# pc_tinyGSR.net
KiCad netlist of a schematic drawn in EAGLE
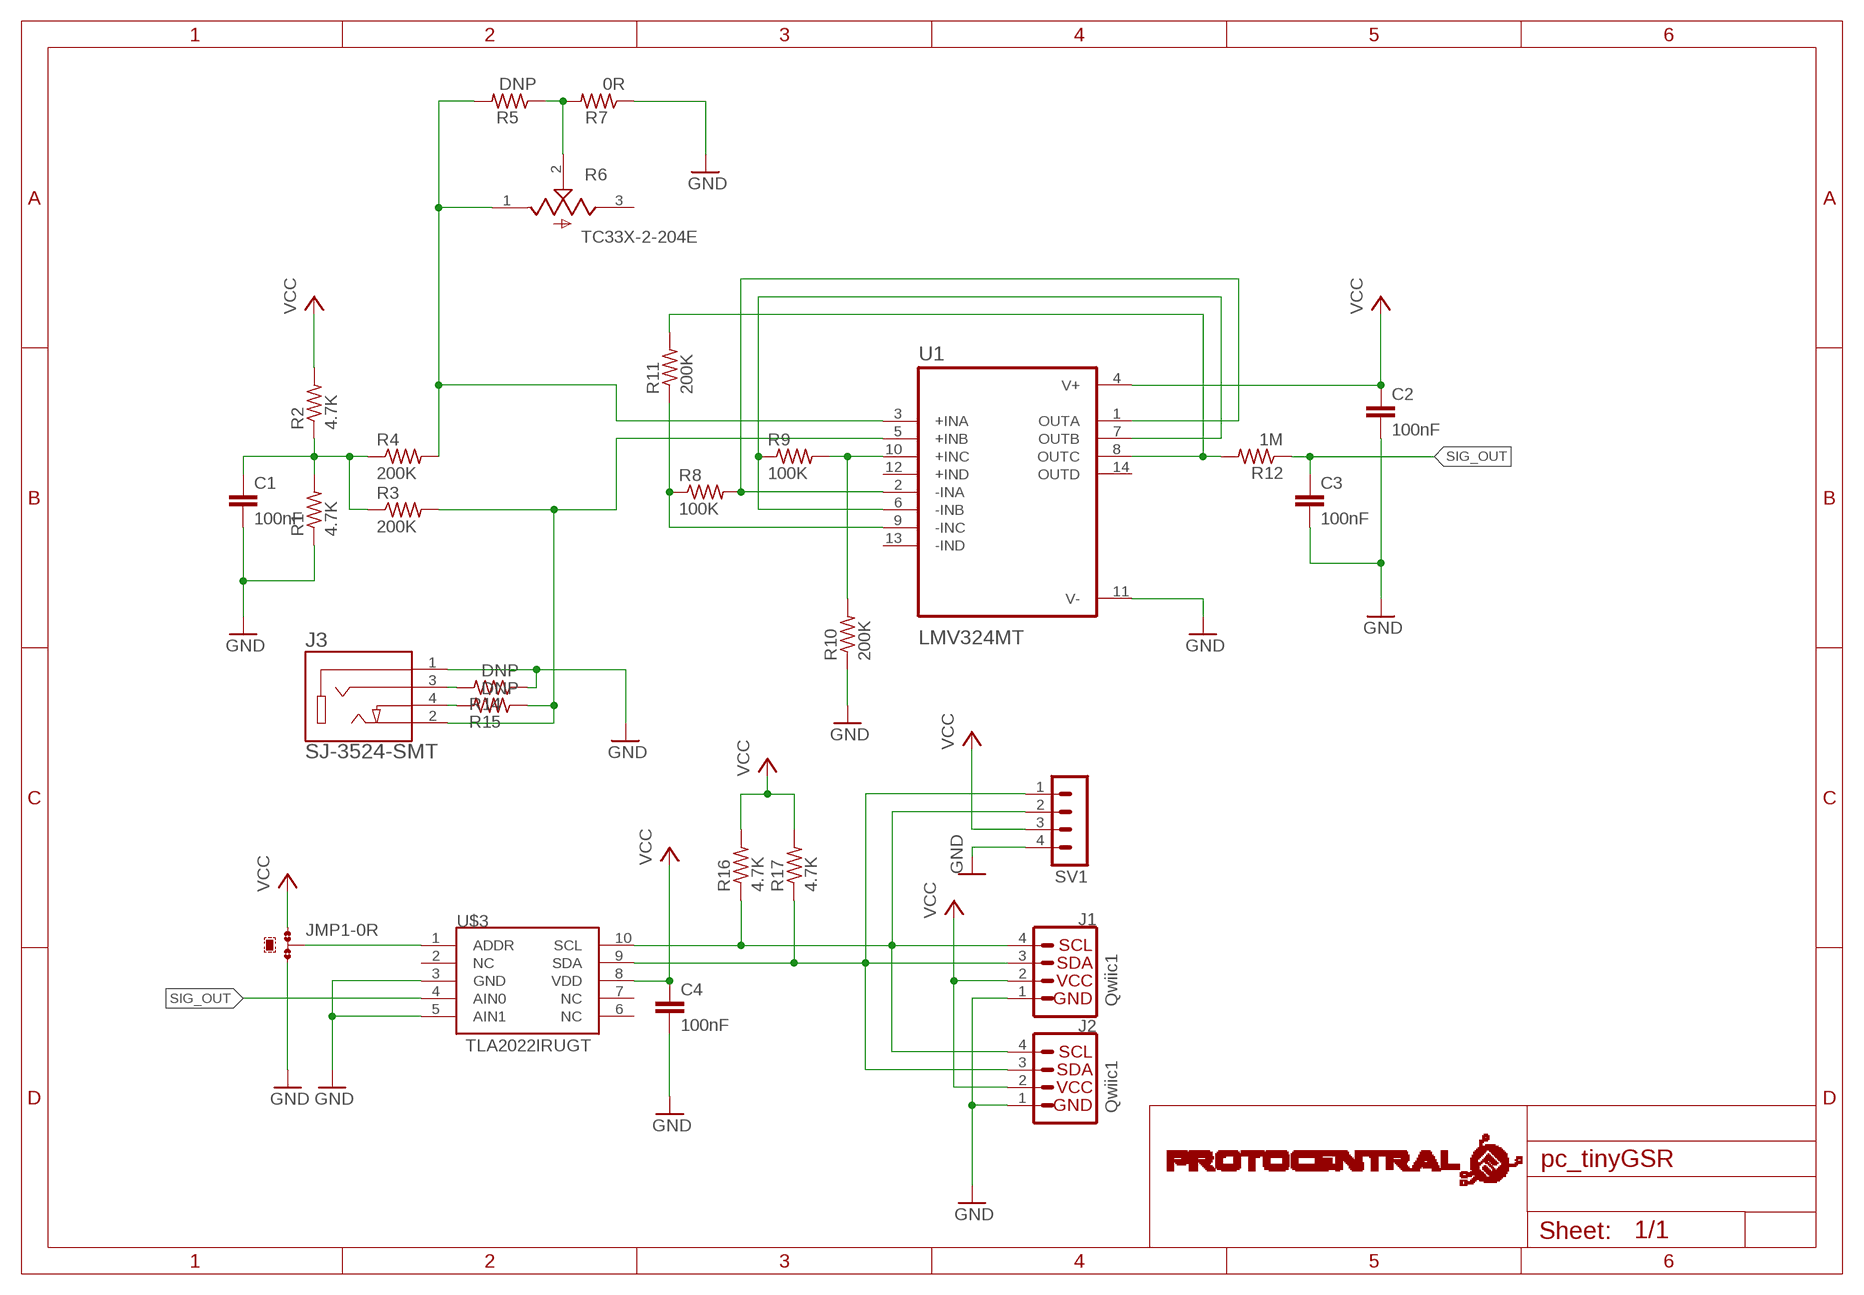
[diagram p0: schematic, sheet 1]

(export (version "E")
  (design (tool "Eeschema 10.0.6"))
  (components
    (comp (ref "C1")
      (value "100nF")
      (footprint "eagle-import:C0402")
      (libsource (lib "eagle-import") (part "C-EUC0402"))
    )
    (comp (ref "C2")
      (value "100nF")
      (footprint "eagle-import:C0402")
      (libsource (lib "eagle-import") (part "C-EUC0402"))
    )
    (comp (ref "C3")
      (value "100nF")
      (footprint "eagle-import:C0402")
      (libsource (lib "eagle-import") (part "C-EUC0402"))
    )
    (comp (ref "C4")
      (value "100nF")
      (footprint "eagle-import:C0402")
      (libsource (lib "eagle-import") (part "C-EUC0402"))
    )
    (comp (ref "J1")
      (value "Qwiic1")
      (footprint "eagle-import:1X04_1MM_RA")
      (libsource (lib "eagle-import") (part "QWIIC_CONNECTORJS-1MM"))
    )
    (comp (ref "J2")
      (value "Qwiic1")
      (footprint "eagle-import:1X04_1MM_RA")
      (libsource (lib "eagle-import") (part "QWIIC_CONNECTORJS-1MM"))
    )
    (comp (ref "J3")
      (value "SJ-3524-SMT")
      (footprint "eagle-import:CUI_SJ-3524-SMT")
      (fields (field (name "MF") "CUI Devices") (field (name "MP") "SJ-3524-SMT-TR"))
      (libsource (lib "eagle-import") (part "SJ-3524-SMT"))
    )
    (comp (ref "JMP1")
      (value "0R-JUMPA")
      (footprint "eagle-import:A0R-JMP")
      (libsource (lib "eagle-import") (part "0R-JUMPA"))
    )
    (comp (ref "R1")
      (value "4.7K")
      (footprint "eagle-import:R0402")
      (libsource (lib "eagle-import") (part "R-US_R0402"))
    )
    (comp (ref "R2")
      (value "4.7K")
      (footprint "eagle-import:R0402")
      (libsource (lib "eagle-import") (part "R-US_R0402"))
    )
    (comp (ref "R3")
      (value "200K")
      (footprint "eagle-import:R0402")
      (libsource (lib "eagle-import") (part "R-US_R0402"))
    )
    (comp (ref "R4")
      (value "200K")
      (footprint "eagle-import:R0402")
      (libsource (lib "eagle-import") (part "R-US_R0402"))
    )
    (comp (ref "R5")
      (value "DNP")
      (footprint "eagle-import:R0402")
      (libsource (lib "eagle-import") (part "R-US_R0402"))
    )
    (comp (ref "R6")
      (value "TC33X-2-204E")
      (footprint "eagle-import:TRIM_TC33X-2-204E")
      (fields (field (name "MF") "Bourns"))
      (libsource (lib "eagle-import") (part "TC33X-2-204E"))
    )
    (comp (ref "R7")
      (value "0R")
      (footprint "eagle-import:R0402")
      (libsource (lib "eagle-import") (part "R-US_R0402"))
    )
    (comp (ref "R8")
      (value "100K")
      (footprint "eagle-import:R0402")
      (libsource (lib "eagle-import") (part "R-US_R0402"))
    )
    (comp (ref "R9")
      (value "100K")
      (footprint "eagle-import:R0402")
      (libsource (lib "eagle-import") (part "R-US_R0402"))
    )
    (comp (ref "R10")
      (value "200K")
      (footprint "eagle-import:R0402")
      (libsource (lib "eagle-import") (part "R-US_R0402"))
    )
    (comp (ref "R11")
      (value "200K")
      (footprint "eagle-import:R0402")
      (libsource (lib "eagle-import") (part "R-US_R0402"))
    )
    (comp (ref "R12")
      (value "1M")
      (footprint "eagle-import:R0402")
      (libsource (lib "eagle-import") (part "R-US_R0402"))
    )
    (comp (ref "R14")
      (value "DNP")
      (footprint "eagle-import:R0402")
      (libsource (lib "eagle-import") (part "R-US_R0402"))
    )
    (comp (ref "R15")
      (value "DNP")
      (footprint "eagle-import:R0402")
      (libsource (lib "eagle-import") (part "R-US_R0402"))
    )
    (comp (ref "R16")
      (value "4.7K")
      (footprint "eagle-import:R0402")
      (libsource (lib "eagle-import") (part "R-US_R0402"))
    )
    (comp (ref "R17")
      (value "4.7K")
      (footprint "eagle-import:R0402")
      (libsource (lib "eagle-import") (part "R-US_R0402"))
    )
    (comp (ref "SV1")
      (value "MA04-1")
      (footprint "eagle-import:MA04-1")
      (libsource (lib "eagle-import") (part "MA04-1"))
    )
    (comp (ref "U$1")
      (value "PROTY_LOGO_WITH_TEXT")
      (footprint "eagle-import:PROTY_WITH_TEXT")
      (libsource (lib "eagle-import") (part "PROTY_LOGO_WITH_TEXT"))
    )
    (comp (ref "U$3")
      (value "TLA2022IRUGT")
      (footprint "eagle-import:QFN50P200X150X40-10N")
      (libsource (lib "eagle-import") (part "TLA2022IRUGT"))
    )
    (comp (ref "U1")
      (value "LMV324MT")
      (footprint "eagle-import:SOP65P640X120-14N")
      (fields (field (name "MF") "Texas Instruments") (field (name "MP") "LMV324MT/NOPB"))
      (libsource (lib "eagle-import") (part "LMV324MT"))
    )
  )
  (nets
    (net (code "1") (name "GND") (class "Default")
      (node (ref "C1") (pin "2") (pinfunction "2_2") (pintype "passive"))
      (node (ref "C2") (pin "2") (pinfunction "2_2") (pintype "passive"))
      (node (ref "C3") (pin "2") (pinfunction "2_2") (pintype "passive"))
      (node (ref "C4") (pin "2") (pinfunction "2_2") (pintype "passive"))
      (node (ref "J1") (pin "1") (pinfunction "1_1") (pintype "power_in"))
      (node (ref "J2") (pin "1") (pinfunction "1_1") (pintype "power_in"))
      (node (ref "J3") (pin "1") (pinfunction "1_1") (pintype "passive"))
      (node (ref "JMP1") (pin "3") (pinfunction "3_3") (pintype "passive"))
      (node (ref "R1") (pin "1") (pinfunction "1_1") (pintype "passive"))
      (node (ref "R10") (pin "1") (pinfunction "1_1") (pintype "passive"))
      (node (ref "R14") (pin "1") (pinfunction "1_1") (pintype "passive"))
      (node (ref "R7") (pin "1") (pinfunction "1_1") (pintype "passive"))
      (node (ref "SV1") (pin "4") (pinfunction "4_4") (pintype "passive"))
      (node (ref "U$3") (pin "3") (pinfunction "GND_3") (pintype "bidirectional"))
      (node (ref "U$3") (pin "5") (pinfunction "AIN1_5") (pintype "bidirectional"))
      (node (ref "U1") (pin "11") (pinfunction "V-_11") (pintype "power_in"))
    )
    (net (code "2") (name "Net-(C1-Pad1)") (class "Default")
      (node (ref "C1") (pin "1") (pinfunction "1_1") (pintype "passive"))
      (node (ref "R1") (pin "2") (pinfunction "2_2") (pintype "passive"))
      (node (ref "R2") (pin "1") (pinfunction "1_1") (pintype "passive"))
      (node (ref "R3") (pin "1") (pinfunction "1_1") (pintype "passive"))
      (node (ref "R4") (pin "1") (pinfunction "1_1") (pintype "passive"))
    )
    (net (code "3") (name "Net-(J3-Pad3)") (class "Default")
      (node (ref "J3") (pin "3") (pinfunction "3_3") (pintype "passive"))
      (node (ref "R14") (pin "2") (pinfunction "2_2") (pintype "passive"))
    )
    (net (code "4") (name "Net-(J3-Pad4)") (class "Default")
      (node (ref "J3") (pin "4") (pinfunction "4_4") (pintype "passive"))
      (node (ref "R15") (pin "2") (pinfunction "2_2") (pintype "passive"))
    )
    (net (code "5") (name "Net-(R6-CCW)") (class "Default")
      (node (ref "R4") (pin "2") (pinfunction "2_2") (pintype "passive"))
      (node (ref "R5") (pin "2") (pinfunction "2_2") (pintype "passive"))
      (node (ref "R6") (pin "1") (pinfunction "CCW_1") (pintype "passive"))
      (node (ref "U1") (pin "3") (pinfunction "+INA_3") (pintype "input"))
    )
    (net (code "6") (name "Net-(R6-W)") (class "Default")
      (node (ref "R5") (pin "1") (pinfunction "1_1") (pintype "passive"))
      (node (ref "R6") (pin "2") (pinfunction "W_2") (pintype "passive"))
      (node (ref "R7") (pin "2") (pinfunction "2_2") (pintype "passive"))
    )
    (net (code "7") (name "Net-(U$3-ADDR)") (class "Default")
      (node (ref "JMP1") (pin "2") (pinfunction "2_2") (pintype "passive"))
      (node (ref "U$3") (pin "1") (pinfunction "ADDR_1") (pintype "bidirectional"))
    )
    (net (code "8") (name "Net-(U$3-SCL)") (class "Default")
      (node (ref "J1") (pin "4") (pinfunction "4_4") (pintype "passive"))
      (node (ref "J2") (pin "4") (pinfunction "4_4") (pintype "passive"))
      (node (ref "R16") (pin "1") (pinfunction "1_1") (pintype "passive"))
      (node (ref "SV1") (pin "2") (pinfunction "2_2") (pintype "passive"))
      (node (ref "U$3") (pin "10") (pinfunction "SCL_10") (pintype "bidirectional"))
    )
    (net (code "9") (name "Net-(U$3-SDA)") (class "Default")
      (node (ref "J1") (pin "3") (pinfunction "3_3") (pintype "passive"))
      (node (ref "J2") (pin "3") (pinfunction "3_3") (pintype "passive"))
      (node (ref "R17") (pin "1") (pinfunction "1_1") (pintype "passive"))
      (node (ref "SV1") (pin "1") (pinfunction "1_1") (pintype "passive"))
      (node (ref "U$3") (pin "9") (pinfunction "SDA_9") (pintype "bidirectional"))
    )
    (net (code "10") (name "Net-(U1-+INB)") (class "Default")
      (node (ref "J3") (pin "2") (pinfunction "2_2") (pintype "passive"))
      (node (ref "R15") (pin "1") (pinfunction "1_1") (pintype "passive"))
      (node (ref "R3") (pin "2") (pinfunction "2_2") (pintype "passive"))
      (node (ref "U1") (pin "5") (pinfunction "+INB_5") (pintype "input"))
    )
    (net (code "11") (name "Net-(U1-+INC)") (class "Default")
      (node (ref "R10") (pin "2") (pinfunction "2_2") (pintype "passive"))
      (node (ref "R9") (pin "2") (pinfunction "2_2") (pintype "passive"))
      (node (ref "U1") (pin "10") (pinfunction "+INC_10") (pintype "input"))
    )
    (net (code "12") (name "Net-(U1--INA)") (class "Default")
      (node (ref "R8") (pin "2") (pinfunction "2_2") (pintype "passive"))
      (node (ref "U1") (pin "1") (pinfunction "OUTA_1") (pintype "output"))
      (node (ref "U1") (pin "2") (pinfunction "-INA_2") (pintype "input"))
    )
    (net (code "13") (name "Net-(U1--INB)") (class "Default")
      (node (ref "R9") (pin "1") (pinfunction "1_1") (pintype "passive"))
      (node (ref "U1") (pin "6") (pinfunction "-INB_6") (pintype "input"))
      (node (ref "U1") (pin "7") (pinfunction "OUTB_7") (pintype "output"))
    )
    (net (code "14") (name "Net-(U1--INC)") (class "Default")
      (node (ref "R11") (pin "1") (pinfunction "1_1") (pintype "passive"))
      (node (ref "R8") (pin "1") (pinfunction "1_1") (pintype "passive"))
      (node (ref "U1") (pin "9") (pinfunction "-INC_9") (pintype "input"))
    )
    (net (code "15") (name "Net-(U1-OUTC)") (class "Default")
      (node (ref "R11") (pin "2") (pinfunction "2_2") (pintype "passive"))
      (node (ref "R12") (pin "2") (pinfunction "2_2") (pintype "passive"))
      (node (ref "U1") (pin "8") (pinfunction "OUTC_8") (pintype "output"))
    )
    (net (code "16") (name "SIG_OUT") (class "Default")
      (node (ref "C3") (pin "1") (pinfunction "1_1") (pintype "passive"))
      (node (ref "R12") (pin "1") (pinfunction "1_1") (pintype "passive"))
      (node (ref "U$3") (pin "4") (pinfunction "AIN0_4") (pintype "bidirectional"))
    )
    (net (code "17") (name "VCC") (class "Default")
      (node (ref "C2") (pin "1") (pinfunction "1_1") (pintype "passive"))
      (node (ref "C4") (pin "1") (pinfunction "1_1") (pintype "passive"))
      (node (ref "J1") (pin "2") (pinfunction "2_2") (pintype "power_in"))
      (node (ref "J2") (pin "2") (pinfunction "2_2") (pintype "power_in"))
      (node (ref "JMP1") (pin "1") (pinfunction "1_1") (pintype "passive"))
      (node (ref "R16") (pin "2") (pinfunction "2_2") (pintype "passive"))
      (node (ref "R17") (pin "2") (pinfunction "2_2") (pintype "passive"))
      (node (ref "R2") (pin "2") (pinfunction "2_2") (pintype "passive"))
      (node (ref "SV1") (pin "3") (pinfunction "3_3") (pintype "passive"))
      (node (ref "U$3") (pin "8") (pinfunction "VDD_8") (pintype "bidirectional"))
      (node (ref "U1") (pin "4") (pinfunction "V+_4") (pintype "power_in"))
    )
    (net (code "18") (name "unconnected-(R6-CW-Pad3)") (class "Default")
      (node (ref "R6") (pin "3") (pinfunction "CW_3") (pintype "passive"))
    )
    (net (code "19") (name "unconnected-(U$3-NC-Pad2)") (class "Default")
      (node (ref "U$3") (pin "2") (pinfunction "NC_2") (pintype "bidirectional"))
    )
    (net (code "20") (name "unconnected-(U$3-NC-Pad6)") (class "Default")
      (node (ref "U$3") (pin "6") (pinfunction "NC_6") (pintype "bidirectional"))
    )
    (net (code "21") (name "unconnected-(U$3-NC-Pad7)") (class "Default")
      (node (ref "U$3") (pin "7") (pinfunction "NC_7") (pintype "bidirectional"))
    )
    (net (code "22") (name "unconnected-(U1-+IND-Pad12)") (class "Default")
      (node (ref "U1") (pin "12") (pinfunction "+IND_12") (pintype "input"))
    )
    (net (code "23") (name "unconnected-(U1--IND-Pad13)") (class "Default")
      (node (ref "U1") (pin "13") (pinfunction "-IND_13") (pintype "input"))
    )
    (net (code "24") (name "unconnected-(U1-OUTD-Pad14)") (class "Default")
      (node (ref "U1") (pin "14") (pinfunction "OUTD_14") (pintype "output"))
    )
  )
)
